# X13_Power_Distribution.net
KiCad netlist of a schematic drawn in EAGLE
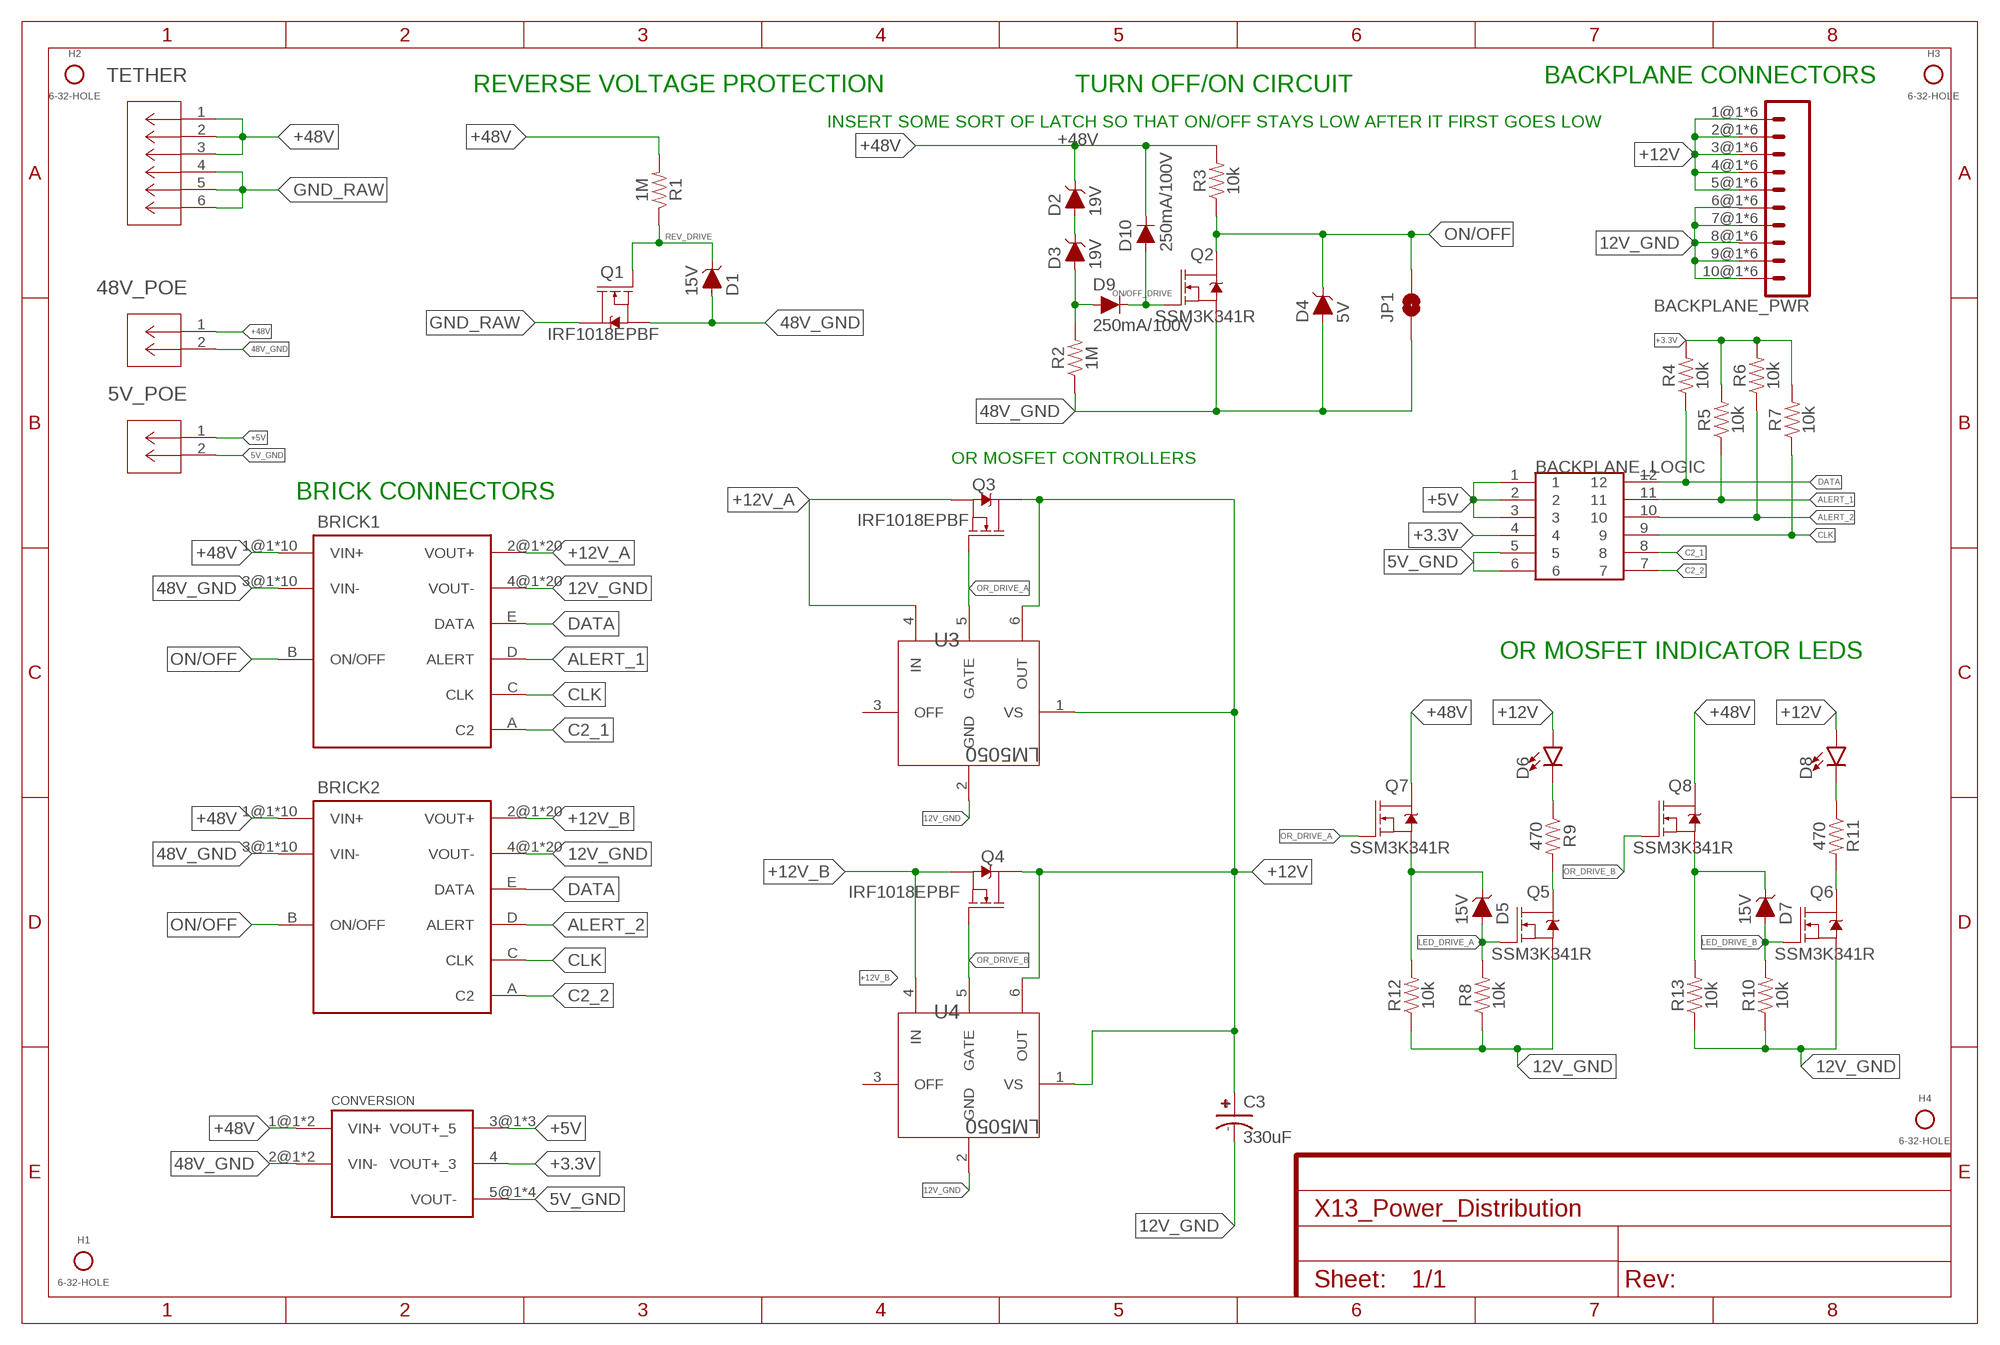
[diagram p0: schematic, sheet 1, part 1 of 2]
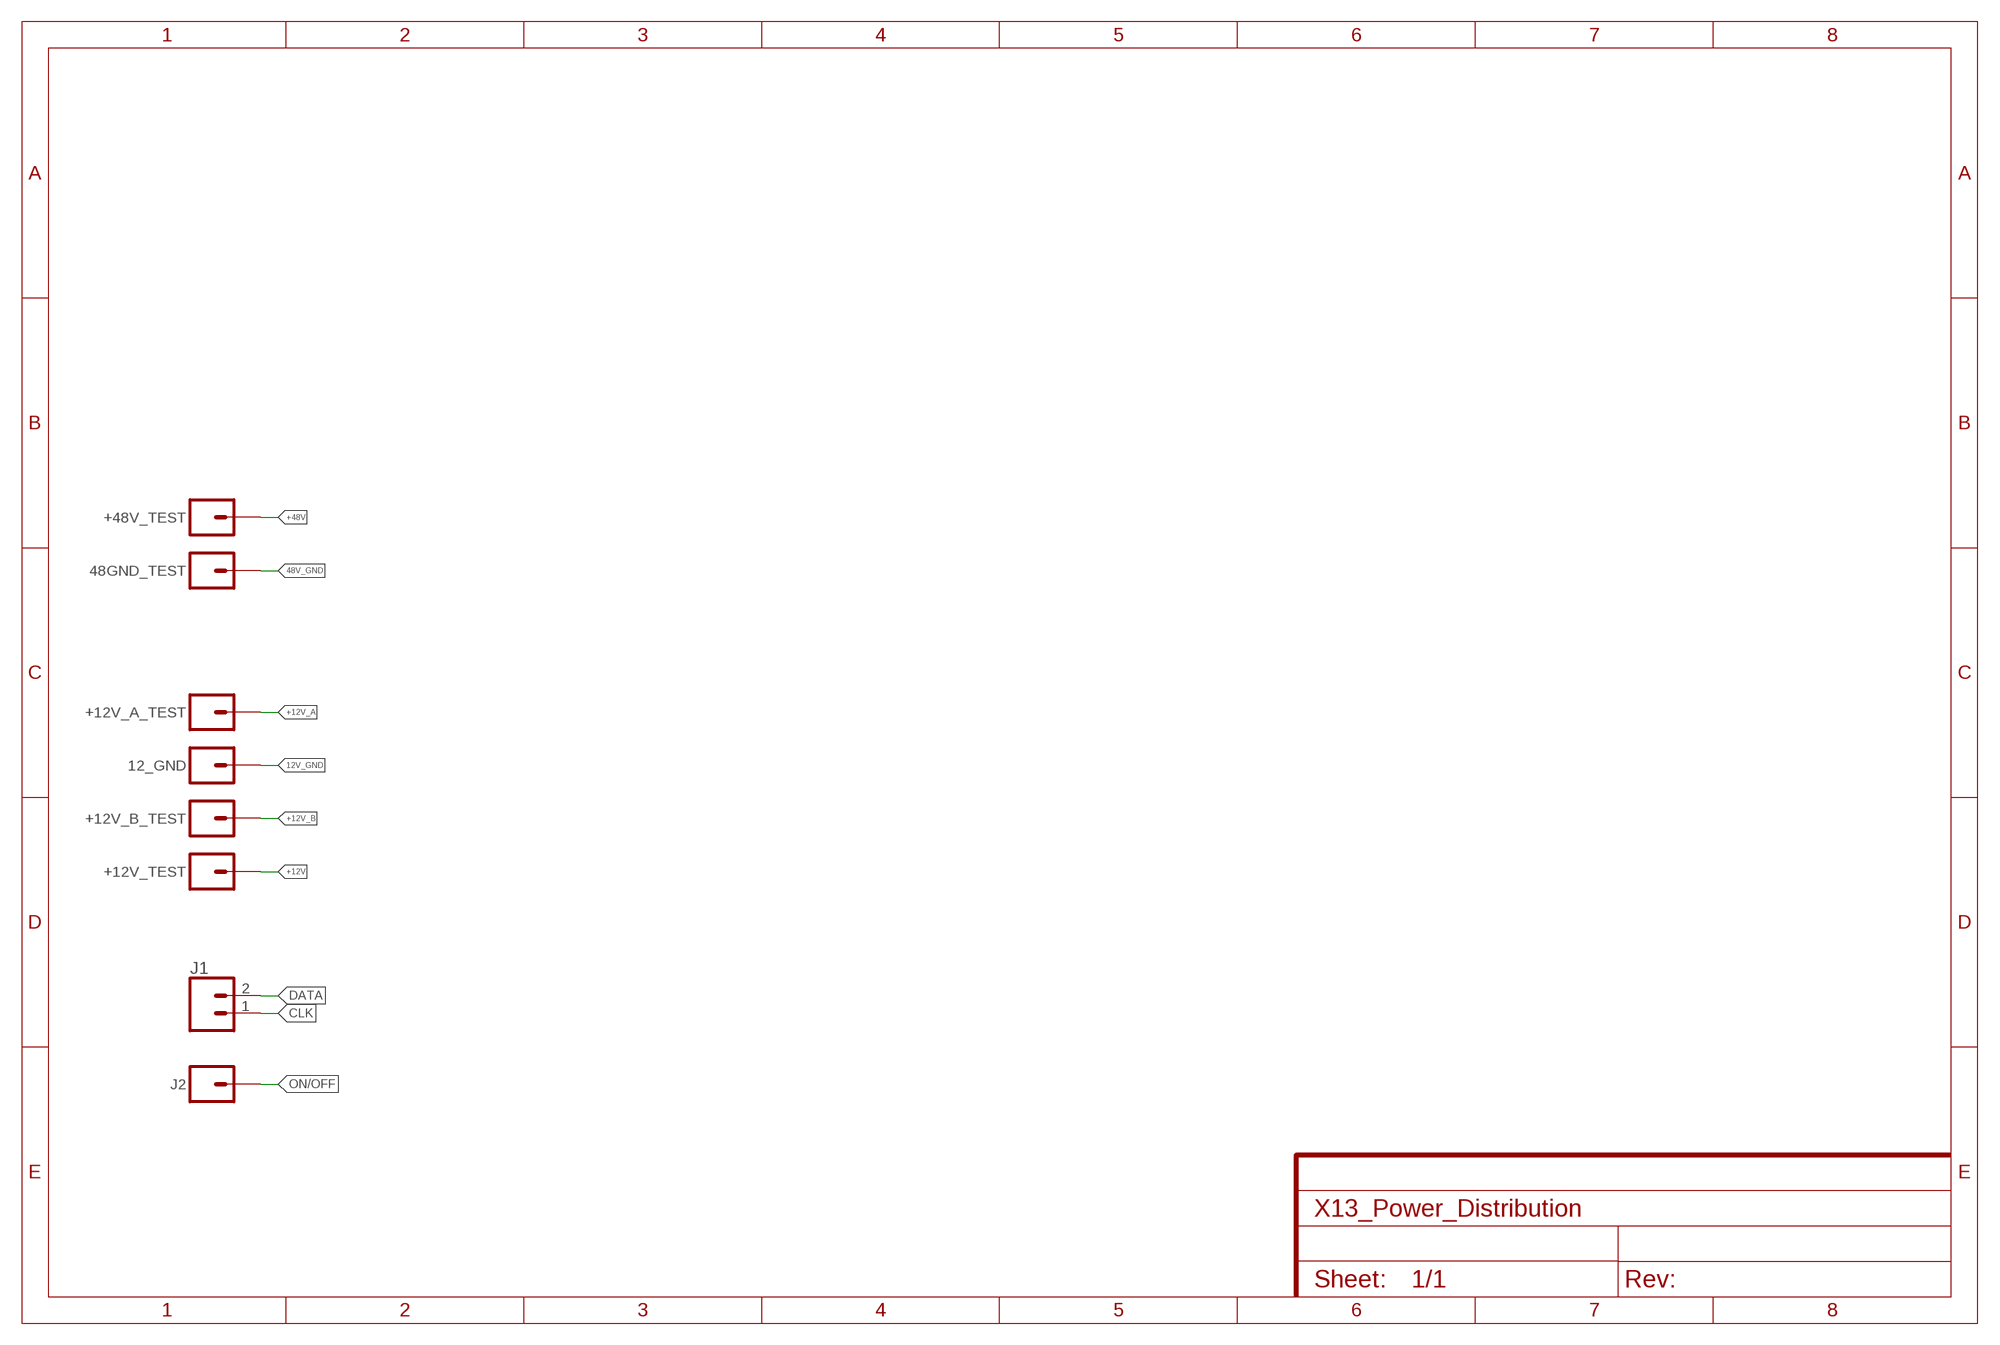
[diagram p1: schematic, sheet 1, part 2 of 2]

(export (version "E")
  (design (tool "Eeschema 10.0.6"))
  (components
    (comp (ref "+12V_A_TEST")
      (value "CONN_01")
      (footprint "eagle-import:1X01")
      (libsource (lib "eagle-import") (part "CONN_01"))
    )
    (comp (ref "+12V_B_TEST")
      (value "CONN_01")
      (footprint "eagle-import:1X01")
      (libsource (lib "eagle-import") (part "CONN_01"))
    )
    (comp (ref "+12V_TEST")
      (value "CONN_01")
      (footprint "eagle-import:1X01")
      (libsource (lib "eagle-import") (part "CONN_01"))
    )
    (comp (ref "+48V_TEST")
      (value "CONN_01")
      (footprint "eagle-import:1X01")
      (libsource (lib "eagle-import") (part "CONN_01"))
    )
    (comp (ref "5V_POE")
      (value "POE_TERMINAL")
      (footprint "eagle-import:CONN2_282834-2_TEC")
      (fields
        (field (name "MANUFACTURER_PART_NUMBER") "282834-2")
        (field (name "COPYRIGHT") "Copyright (C) 2016 Accelerated Designs. All rights reserved")
      )
      (libsource (lib "eagle-import") (part "POE_TERMINAL"))
    )
    (comp (ref "12_GND")
      (value "CONN_01")
      (footprint "eagle-import:1X01")
      (libsource (lib "eagle-import") (part "CONN_01"))
    )
    (comp (ref "48GND_TEST")
      (value "CONN_01")
      (footprint "eagle-import:1X01")
      (libsource (lib "eagle-import") (part "CONN_01"))
    )
    (comp (ref "48V_POE")
      (value "POE_TERMINAL")
      (footprint "eagle-import:CONN2_282834-2_TEC")
      (fields
        (field (name "MANUFACTURER_PART_NUMBER") "282834-2")
        (field (name "COPYRIGHT") "Copyright (C) 2016 Accelerated Designs. All rights reserved")
      )
      (libsource (lib "eagle-import") (part "POE_TERMINAL"))
    )
    (comp (ref "BACKPLANE_LOGIC")
      (value "IPL1-106-01-L-D-K")
      (footprint "eagle-import:IPL1-106-01-L-D-K")
      (libsource (lib "eagle-import") (part "IPL1-106-01-L-D-K"))
    )
    (comp (ref "BACKPLANE_PWR")
      (value "MPPT-10-01-01-L-RA-SD")
      (footprint "eagle-import:MPPT-10-01-01-L-RA-SD")
      (libsource (lib "eagle-import") (part "MPPT-10-01-01-L-RA-SD"))
    )
    (comp (ref "BRICK1")
      (value "DIST2BRICKVER_D2")
      (footprint "eagle-import:DIST2BRICK_D2")
      (libsource (lib "eagle-import") (part "DIST2BRICKVER_D2"))
    )
    (comp (ref "BRICK2")
      (value "DIST2BRICKVER_D2")
      (footprint "eagle-import:DIST2BRICK_D2")
      (libsource (lib "eagle-import") (part "DIST2BRICKVER_D2"))
    )
    (comp (ref "C3")
      (value "330uF")
      (footprint "eagle-import:CAPAE1030X1050N")
      (fields
        (field (name "ARROW_PART_NUMBER") "UCM1H331MNL1GS")
        (field (name "MOUSER_PART_NUMBER") "647-UCM1H331MNL1GS")
      )
      (libsource (lib "eagle-import") (part "UCM1H331MNL1GS"))
    )
    (comp (ref "CONVERSION")
      (value "DIST2CON")
      (footprint "eagle-import:DIST2CON")
      (libsource (lib "eagle-import") (part "DIST2CON"))
    )
    (comp (ref "D1")
      (value "15V")
      (footprint "eagle-import:SOD-323")
      (libsource (lib "eagle-import") (part "DIODE-ZENER-BZT52C3V6S"))
    )
    (comp (ref "D2")
      (value "19V")
      (footprint "eagle-import:SOD-323")
      (libsource (lib "eagle-import") (part "DIODE-ZENER-BZT52C3V6S"))
    )
    (comp (ref "D3")
      (value "19V")
      (footprint "eagle-import:SOD-323")
      (libsource (lib "eagle-import") (part "DIODE-ZENER-BZT52C3V6S"))
    )
    (comp (ref "D4")
      (value "5V")
      (footprint "eagle-import:SOD-323")
      (libsource (lib "eagle-import") (part "DIODE-ZENER-BZT52C3V6S"))
    )
    (comp (ref "D5")
      (value "15V")
      (footprint "eagle-import:SOD-323")
      (libsource (lib "eagle-import") (part "DIODE-ZENER-BZT52C3V6S"))
    )
    (comp (ref "D6")
      (value "LED0603")
      (footprint "eagle-import:LED-0603")
      (libsource (lib "eagle-import") (part "LED0603"))
    )
    (comp (ref "D7")
      (value "15V")
      (footprint "eagle-import:SOD-323")
      (libsource (lib "eagle-import") (part "DIODE-ZENER-BZT52C3V6S"))
    )
    (comp (ref "D8")
      (value "LED0603")
      (footprint "eagle-import:LED-0603")
      (libsource (lib "eagle-import") (part "LED0603"))
    )
    (comp (ref "D9")
      (value "250mA/100V")
      (footprint "eagle-import:SOD-323")
      (libsource (lib "eagle-import") (part "DIODE-BAS16J"))
    )
    (comp (ref "D10")
      (value "250mA/100V")
      (footprint "eagle-import:SOD-323")
      (libsource (lib "eagle-import") (part "DIODE-BAS16J"))
    )
    (comp (ref "H1")
      (value "6-32-HOLE")
      (footprint "eagle-import:6-32-HOLE")
      (libsource (lib "eagle-import") (part "6-32-HOLE"))
    )
    (comp (ref "H2")
      (value "6-32-HOLE")
      (footprint "eagle-import:6-32-HOLE")
      (libsource (lib "eagle-import") (part "6-32-HOLE"))
    )
    (comp (ref "H3")
      (value "6-32-HOLE")
      (footprint "eagle-import:6-32-HOLE")
      (libsource (lib "eagle-import") (part "6-32-HOLE"))
    )
    (comp (ref "H4")
      (value "6-32-HOLE")
      (footprint "eagle-import:6-32-HOLE")
      (libsource (lib "eagle-import") (part "6-32-HOLE"))
    )
    (comp (ref "J1")
      (value "CONN_02")
      (footprint "eagle-import:1X02")
      (libsource (lib "eagle-import") (part "CONN_02"))
    )
    (comp (ref "J2")
      (value "CONN_01")
      (footprint "eagle-import:1X01")
      (libsource (lib "eagle-import") (part "CONN_01"))
    )
    (comp (ref "JP1")
      (value "JUMPER-SMT_2_NO_SILK")
      (footprint "eagle-import:SMT-JUMPER_2_NO_SILK")
      (libsource (lib "eagle-import") (part "JUMPER-SMT_2_NO_SILK"))
    )
    (comp (ref "Q1")
      (value "IRF1018EPBF")
      (footprint "eagle-import:TO263")
      (libsource (lib "eagle-import") (part "IRF1018EPBF"))
    )
    (comp (ref "Q2")
      (value "SSM3K341R")
      (footprint "eagle-import:SOT323")
      (libsource (lib "eagle-import") (part "MOSFET-NCH-2N7002PW"))
    )
    (comp (ref "Q3")
      (value "IRF1018EPBF")
      (footprint "eagle-import:TO263")
      (libsource (lib "eagle-import") (part "IRF1018EPBF"))
    )
    (comp (ref "Q4")
      (value "IRF1018EPBF")
      (footprint "eagle-import:TO263")
      (libsource (lib "eagle-import") (part "IRF1018EPBF"))
    )
    (comp (ref "Q5")
      (value "SSM3K341R")
      (footprint "eagle-import:SOT323")
      (libsource (lib "eagle-import") (part "MOSFET-NCH-2N7002PW"))
    )
    (comp (ref "Q6")
      (value "SSM3K341R")
      (footprint "eagle-import:SOT323")
      (libsource (lib "eagle-import") (part "MOSFET-NCH-2N7002PW"))
    )
    (comp (ref "Q7")
      (value "SSM3K341R")
      (footprint "eagle-import:SOT323")
      (libsource (lib "eagle-import") (part "MOSFET-NCH-2N7002PW"))
    )
    (comp (ref "Q8")
      (value "SSM3K341R")
      (footprint "eagle-import:SOT323")
      (libsource (lib "eagle-import") (part "MOSFET-NCH-2N7002PW"))
    )
    (comp (ref "R1")
      (value "1M")
      (footprint "eagle-import:0603")
      (libsource (lib "eagle-import") (part "RESISTOR0603"))
    )
    (comp (ref "R2")
      (value "1M")
      (footprint "eagle-import:0603")
      (fields (field (name "SPICEPREFIX") "R"))
      (libsource (lib "eagle-import") (part "RESISTOR0603"))
    )
    (comp (ref "R3")
      (value "10k")
      (footprint "eagle-import:0603")
      (fields (field (name "SPICEPREFIX") "R"))
      (libsource (lib "eagle-import") (part "RESISTOR0603"))
    )
    (comp (ref "R4")
      (value "10k")
      (footprint "eagle-import:0603")
      (libsource (lib "eagle-import") (part "RESISTOR0603"))
    )
    (comp (ref "R5")
      (value "10k")
      (footprint "eagle-import:0603")
      (libsource (lib "eagle-import") (part "RESISTOR0603"))
    )
    (comp (ref "R6")
      (value "10k")
      (footprint "eagle-import:0603")
      (libsource (lib "eagle-import") (part "RESISTOR0603"))
    )
    (comp (ref "R7")
      (value "10k")
      (footprint "eagle-import:0603")
      (libsource (lib "eagle-import") (part "RESISTOR0603"))
    )
    (comp (ref "R8")
      (value "10k")
      (footprint "eagle-import:0603")
      (fields (field (name "SPICEPREFIX") "R"))
      (libsource (lib "eagle-import") (part "RESISTOR0603"))
    )
    (comp (ref "R9")
      (value "470")
      (footprint "eagle-import:0603")
      (libsource (lib "eagle-import") (part "RESISTOR0603"))
    )
    (comp (ref "R10")
      (value "10k")
      (footprint "eagle-import:0603")
      (fields (field (name "SPICEPREFIX") "R"))
      (libsource (lib "eagle-import") (part "RESISTOR0603"))
    )
    (comp (ref "R11")
      (value "470")
      (footprint "eagle-import:0603")
      (libsource (lib "eagle-import") (part "RESISTOR0603"))
    )
    (comp (ref "R12")
      (value "10k")
      (footprint "eagle-import:0603")
      (fields (field (name "SPICEPREFIX") "R"))
      (libsource (lib "eagle-import") (part "RESISTOR0603"))
    )
    (comp (ref "R13")
      (value "10k")
      (footprint "eagle-import:0603")
      (fields (field (name "SPICEPREFIX") "R"))
      (libsource (lib "eagle-import") (part "RESISTOR0603"))
    )
    (comp (ref "TETHER")
      (value "48V")
      (footprint "eagle-import:CON6_P5MM_VER_TERM-BLK_TYC")
      (fields (field (name "MANUFACTURER_PART_NUMBER") "796636-6"))
      (libsource (lib "eagle-import") (part "DIST_TO_TETHER"))
    )
    (comp (ref "U3")
      (value "LM5050")
      (footprint "eagle-import:SOT-23-6")
      (fields
        (field (name "MANUFACTURER") "Texas Instruments")
        (field (name "MANUFACTURER_PART_NUMBER") "LM5050MK-1/NOPB")
      )
      (libsource (lib "eagle-import") (part "DIST_OR_CONTROL_ALTMK06A-M"))
    )
    (comp (ref "U4")
      (value "LM5050")
      (footprint "eagle-import:SOT-23-6")
      (fields
        (field (name "MANUFACTURER") "Texas Instruments")
        (field (name "MANUFACTURER_PART_NUMBER") "LM5050MK-1/NOPB")
      )
      (libsource (lib "eagle-import") (part "DIST_OR_CONTROL_ALTMK06A-M"))
    )
  )
  (nets
    (net (code "1") (name "+3.3V") (class "Default")
      (node (ref "BACKPLANE_LOGIC") (pin "4") (pinfunction "4_4") (pintype "bidirectional"))
      (node (ref "CONVERSION") (pin "4") (pinfunction "VOUT+_3_4") (pintype "bidirectional"))
      (node (ref "R4") (pin "2") (pinfunction "2_2") (pintype "passive"))
      (node (ref "R5") (pin "2") (pinfunction "2_2") (pintype "passive"))
      (node (ref "R6") (pin "2") (pinfunction "2_2") (pintype "passive"))
      (node (ref "R7") (pin "2") (pinfunction "2_2") (pintype "passive"))
    )
    (net (code "2") (name "+5V") (class "Default")
      (node (ref "5V_POE") (pin "1") (pinfunction "1_1") (pintype "passive"))
      (node (ref "BACKPLANE_LOGIC") (pin "1") (pinfunction "1_1") (pintype "bidirectional"))
      (node (ref "BACKPLANE_LOGIC") (pin "2") (pinfunction "2_2") (pintype "bidirectional"))
      (node (ref "BACKPLANE_LOGIC") (pin "3") (pinfunction "3_3") (pintype "bidirectional"))
      (node (ref "CONVERSION") (pin "3@1") (pinfunction "VOUT+_5_3@1") (pintype "bidirectional"))
      (node (ref "CONVERSION") (pin "3@2") (pinfunction "VOUT+_5_3@2") (pintype "bidirectional"))
      (node (ref "CONVERSION") (pin "3@3") (pinfunction "VOUT+_5_3@3") (pintype "bidirectional"))
    )
    (net (code "3") (name "+12V") (class "Default")
      (node (ref "+12V_TEST") (pin "1") (pinfunction "1_1") (pintype "passive"))
      (node (ref "BACKPLANE_PWR") (pin "1@1") (pinfunction "1_1@1") (pintype "passive"))
      (node (ref "BACKPLANE_PWR") (pin "1@2") (pinfunction "1_1@2") (pintype "passive"))
      (node (ref "BACKPLANE_PWR") (pin "1@3") (pinfunction "1_1@3") (pintype "passive"))
      (node (ref "BACKPLANE_PWR") (pin "1@4") (pinfunction "1_1@4") (pintype "passive"))
      (node (ref "BACKPLANE_PWR") (pin "1@5") (pinfunction "1_1@5") (pintype "passive"))
      (node (ref "BACKPLANE_PWR") (pin "1@6") (pinfunction "1_1@6") (pintype "passive"))
      (node (ref "BACKPLANE_PWR") (pin "2@1") (pinfunction "2_2@1") (pintype "passive"))
      (node (ref "BACKPLANE_PWR") (pin "2@2") (pinfunction "2_2@2") (pintype "passive"))
      (node (ref "BACKPLANE_PWR") (pin "2@3") (pinfunction "2_2@3") (pintype "passive"))
      (node (ref "BACKPLANE_PWR") (pin "2@4") (pinfunction "2_2@4") (pintype "passive"))
      (node (ref "BACKPLANE_PWR") (pin "2@5") (pinfunction "2_2@5") (pintype "passive"))
      (node (ref "BACKPLANE_PWR") (pin "2@6") (pinfunction "2_2@6") (pintype "passive"))
      (node (ref "BACKPLANE_PWR") (pin "3@1") (pinfunction "3_3@1") (pintype "passive"))
      (node (ref "BACKPLANE_PWR") (pin "3@2") (pinfunction "3_3@2") (pintype "passive"))
      (node (ref "BACKPLANE_PWR") (pin "3@3") (pinfunction "3_3@3") (pintype "passive"))
      (node (ref "BACKPLANE_PWR") (pin "3@4") (pinfunction "3_3@4") (pintype "passive"))
      (node (ref "BACKPLANE_PWR") (pin "3@5") (pinfunction "3_3@5") (pintype "passive"))
      (node (ref "BACKPLANE_PWR") (pin "3@6") (pinfunction "3_3@6") (pintype "passive"))
      (node (ref "BACKPLANE_PWR") (pin "4@1") (pinfunction "4_4@1") (pintype "passive"))
      (node (ref "BACKPLANE_PWR") (pin "4@2") (pinfunction "4_4@2") (pintype "passive"))
      (node (ref "BACKPLANE_PWR") (pin "4@3") (pinfunction "4_4@3") (pintype "passive"))
      (node (ref "BACKPLANE_PWR") (pin "4@4") (pinfunction "4_4@4") (pintype "passive"))
      (node (ref "BACKPLANE_PWR") (pin "4@5") (pinfunction "4_4@5") (pintype "passive"))
      (node (ref "BACKPLANE_PWR") (pin "4@6") (pinfunction "4_4@6") (pintype "passive"))
      (node (ref "BACKPLANE_PWR") (pin "5@1") (pinfunction "5_5@1") (pintype "passive"))
      (node (ref "BACKPLANE_PWR") (pin "5@2") (pinfunction "5_5@2") (pintype "passive"))
      (node (ref "BACKPLANE_PWR") (pin "5@3") (pinfunction "5_5@3") (pintype "passive"))
      (node (ref "BACKPLANE_PWR") (pin "5@4") (pinfunction "5_5@4") (pintype "passive"))
      (node (ref "BACKPLANE_PWR") (pin "5@5") (pinfunction "5_5@5") (pintype "passive"))
      (node (ref "BACKPLANE_PWR") (pin "5@6") (pinfunction "5_5@6") (pintype "passive"))
      (node (ref "C3") (pin "+") (pinfunction "+_+") (pintype "bidirectional"))
      (node (ref "D6") (pin "A") (pinfunction "A_A") (pintype "passive"))
      (node (ref "D8") (pin "A") (pinfunction "A_A") (pintype "passive"))
      (node (ref "Q3") (pin "3") (pinfunction "D_3") (pintype "bidirectional"))
      (node (ref "Q4") (pin "3") (pinfunction "D_3") (pintype "bidirectional"))
      (node (ref "U3") (pin "1") (pinfunction "VS_1") (pintype "passive"))
      (node (ref "U3") (pin "6") (pinfunction "OUT_6") (pintype "output"))
      (node (ref "U4") (pin "1") (pinfunction "VS_1") (pintype "passive"))
      (node (ref "U4") (pin "6") (pinfunction "OUT_6") (pintype "output"))
    )
    (net (code "4") (name "+12V_A") (class "Default")
      (node (ref "+12V_A_TEST") (pin "1") (pinfunction "1_1") (pintype "passive"))
      (node (ref "BRICK1") (pin "2@1") (pinfunction "VOUT+_2@1") (pintype "bidirectional"))
      (node (ref "BRICK1") (pin "2@10") (pinfunction "VOUT+_2@10") (pintype "bidirectional"))
      (node (ref "BRICK1") (pin "2@11") (pinfunction "VOUT+_2@11") (pintype "bidirectional"))
      (node (ref "BRICK1") (pin "2@12") (pinfunction "VOUT+_2@12") (pintype "bidirectional"))
      (node (ref "BRICK1") (pin "2@13") (pinfunction "VOUT+_2@13") (pintype "bidirectional"))
      (node (ref "BRICK1") (pin "2@14") (pinfunction "VOUT+_2@14") (pintype "bidirectional"))
      (node (ref "BRICK1") (pin "2@15") (pinfunction "VOUT+_2@15") (pintype "bidirectional"))
      (node (ref "BRICK1") (pin "2@16") (pinfunction "VOUT+_2@16") (pintype "bidirectional"))
      (node (ref "BRICK1") (pin "2@17") (pinfunction "VOUT+_2@17") (pintype "bidirectional"))
      (node (ref "BRICK1") (pin "2@18") (pinfunction "VOUT+_2@18") (pintype "bidirectional"))
      (node (ref "BRICK1") (pin "2@19") (pinfunction "VOUT+_2@19") (pintype "bidirectional"))
      (node (ref "BRICK1") (pin "2@2") (pinfunction "VOUT+_2@2") (pintype "bidirectional"))
      (node (ref "BRICK1") (pin "2@20") (pinfunction "VOUT+_2@20") (pintype "bidirectional"))
      (node (ref "BRICK1") (pin "2@3") (pinfunction "VOUT+_2@3") (pintype "bidirectional"))
      (node (ref "BRICK1") (pin "2@4") (pinfunction "VOUT+_2@4") (pintype "bidirectional"))
      (node (ref "BRICK1") (pin "2@5") (pinfunction "VOUT+_2@5") (pintype "bidirectional"))
      (node (ref "BRICK1") (pin "2@6") (pinfunction "VOUT+_2@6") (pintype "bidirectional"))
      (node (ref "BRICK1") (pin "2@7") (pinfunction "VOUT+_2@7") (pintype "bidirectional"))
      (node (ref "BRICK1") (pin "2@8") (pinfunction "VOUT+_2@8") (pintype "bidirectional"))
      (node (ref "BRICK1") (pin "2@9") (pinfunction "VOUT+_2@9") (pintype "bidirectional"))
      (node (ref "Q3") (pin "2") (pinfunction "S_2") (pintype "bidirectional"))
      (node (ref "U3") (pin "4") (pinfunction "IN_4") (pintype "input"))
    )
    (net (code "5") (name "+12V_B") (class "Default")
      (node (ref "+12V_B_TEST") (pin "1") (pinfunction "1_1") (pintype "passive"))
      (node (ref "BRICK2") (pin "2@1") (pinfunction "VOUT+_2@1") (pintype "bidirectional"))
      (node (ref "BRICK2") (pin "2@10") (pinfunction "VOUT+_2@10") (pintype "bidirectional"))
      (node (ref "BRICK2") (pin "2@11") (pinfunction "VOUT+_2@11") (pintype "bidirectional"))
      (node (ref "BRICK2") (pin "2@12") (pinfunction "VOUT+_2@12") (pintype "bidirectional"))
      (node (ref "BRICK2") (pin "2@13") (pinfunction "VOUT+_2@13") (pintype "bidirectional"))
      (node (ref "BRICK2") (pin "2@14") (pinfunction "VOUT+_2@14") (pintype "bidirectional"))
      (node (ref "BRICK2") (pin "2@15") (pinfunction "VOUT+_2@15") (pintype "bidirectional"))
      (node (ref "BRICK2") (pin "2@16") (pinfunction "VOUT+_2@16") (pintype "bidirectional"))
      (node (ref "BRICK2") (pin "2@17") (pinfunction "VOUT+_2@17") (pintype "bidirectional"))
      (node (ref "BRICK2") (pin "2@18") (pinfunction "VOUT+_2@18") (pintype "bidirectional"))
      (node (ref "BRICK2") (pin "2@19") (pinfunction "VOUT+_2@19") (pintype "bidirectional"))
      (node (ref "BRICK2") (pin "2@2") (pinfunction "VOUT+_2@2") (pintype "bidirectional"))
      (node (ref "BRICK2") (pin "2@20") (pinfunction "VOUT+_2@20") (pintype "bidirectional"))
      (node (ref "BRICK2") (pin "2@3") (pinfunction "VOUT+_2@3") (pintype "bidirectional"))
      (node (ref "BRICK2") (pin "2@4") (pinfunction "VOUT+_2@4") (pintype "bidirectional"))
      (node (ref "BRICK2") (pin "2@5") (pinfunction "VOUT+_2@5") (pintype "bidirectional"))
      (node (ref "BRICK2") (pin "2@6") (pinfunction "VOUT+_2@6") (pintype "bidirectional"))
      (node (ref "BRICK2") (pin "2@7") (pinfunction "VOUT+_2@7") (pintype "bidirectional"))
      (node (ref "BRICK2") (pin "2@8") (pinfunction "VOUT+_2@8") (pintype "bidirectional"))
      (node (ref "BRICK2") (pin "2@9") (pinfunction "VOUT+_2@9") (pintype "bidirectional"))
      (node (ref "Q4") (pin "2") (pinfunction "S_2") (pintype "bidirectional"))
      (node (ref "U4") (pin "4") (pinfunction "IN_4") (pintype "input"))
    )
    (net (code "6") (name "+48V") (class "Default")
      (node (ref "+48V_TEST") (pin "1") (pinfunction "1_1") (pintype "passive"))
      (node (ref "48V_POE") (pin "1") (pinfunction "1_1") (pintype "passive"))
      (node (ref "BRICK1") (pin "1@1") (pinfunction "VIN+_1@1") (pintype "bidirectional"))
      (node (ref "BRICK1") (pin "1@10") (pinfunction "VIN+_1@10") (pintype "bidirectional"))
      (node (ref "BRICK1") (pin "1@2") (pinfunction "VIN+_1@2") (pintype "bidirectional"))
      (node (ref "BRICK1") (pin "1@3") (pinfunction "VIN+_1@3") (pintype "bidirectional"))
      (node (ref "BRICK1") (pin "1@4") (pinfunction "VIN+_1@4") (pintype "bidirectional"))
      (node (ref "BRICK1") (pin "1@5") (pinfunction "VIN+_1@5") (pintype "bidirectional"))
      (node (ref "BRICK1") (pin "1@6") (pinfunction "VIN+_1@6") (pintype "bidirectional"))
      (node (ref "BRICK1") (pin "1@7") (pinfunction "VIN+_1@7") (pintype "bidirectional"))
      (node (ref "BRICK1") (pin "1@8") (pinfunction "VIN+_1@8") (pintype "bidirectional"))
      (node (ref "BRICK1") (pin "1@9") (pinfunction "VIN+_1@9") (pintype "bidirectional"))
      (node (ref "BRICK2") (pin "1@1") (pinfunction "VIN+_1@1") (pintype "bidirectional"))
      (node (ref "BRICK2") (pin "1@10") (pinfunction "VIN+_1@10") (pintype "bidirectional"))
      (node (ref "BRICK2") (pin "1@2") (pinfunction "VIN+_1@2") (pintype "bidirectional"))
      (node (ref "BRICK2") (pin "1@3") (pinfunction "VIN+_1@3") (pintype "bidirectional"))
      (node (ref "BRICK2") (pin "1@4") (pinfunction "VIN+_1@4") (pintype "bidirectional"))
      (node (ref "BRICK2") (pin "1@5") (pinfunction "VIN+_1@5") (pintype "bidirectional"))
      (node (ref "BRICK2") (pin "1@6") (pinfunction "VIN+_1@6") (pintype "bidirectional"))
      (node (ref "BRICK2") (pin "1@7") (pinfunction "VIN+_1@7") (pintype "bidirectional"))
      (node (ref "BRICK2") (pin "1@8") (pinfunction "VIN+_1@8") (pintype "bidirectional"))
      (node (ref "BRICK2") (pin "1@9") (pinfunction "VIN+_1@9") (pintype "bidirectional"))
      (node (ref "CONVERSION") (pin "1@1") (pinfunction "VIN+_1@1") (pintype "bidirectional"))
      (node (ref "CONVERSION") (pin "1@2") (pinfunction "VIN+_1@2") (pintype "bidirectional"))
      (node (ref "D10") (pin "C") (pinfunction "C_C") (pintype "passive"))
      (node (ref "D2") (pin "C") (pinfunction "C_C") (pintype "passive"))
      (node (ref "Q7") (pin "3") (pinfunction "D_3") (pintype "bidirectional"))
      (node (ref "Q8") (pin "3") (pinfunction "D_3") (pintype "bidirectional"))
      (node (ref "R1") (pin "2") (pinfunction "2_2") (pintype "passive"))
      (node (ref "R3") (pin "2") (pinfunction "2_2") (pintype "passive"))
      (node (ref "TETHER") (pin "1") (pinfunction "1_1") (pintype "passive"))
      (node (ref "TETHER") (pin "2") (pinfunction "2_2") (pintype "passive"))
      (node (ref "TETHER") (pin "3") (pinfunction "3_3") (pintype "passive"))
    )
    (net (code "7") (name "/ON{slash}OFF_DRIVE") (class "Default")
      (node (ref "D10") (pin "A") (pinfunction "A_A") (pintype "passive"))
      (node (ref "D9") (pin "C") (pinfunction "C_C") (pintype "passive"))
      (node (ref "Q2") (pin "1") (pinfunction "G_1") (pintype "bidirectional"))
    )
    (net (code "8") (name "/REV_DRIVE") (class "Default")
      (node (ref "D1") (pin "C") (pinfunction "C_C") (pintype "passive"))
      (node (ref "Q1") (pin "1") (pinfunction "G_1") (pintype "bidirectional"))
      (node (ref "R1") (pin "1") (pinfunction "1_1") (pintype "passive"))
    )
    (net (code "9") (name "5V_GND") (class "Default")
      (node (ref "5V_POE") (pin "2") (pinfunction "2_2") (pintype "passive"))
      (node (ref "BACKPLANE_LOGIC") (pin "5") (pinfunction "5_5") (pintype "bidirectional"))
      (node (ref "BACKPLANE_LOGIC") (pin "6") (pinfunction "6_6") (pintype "bidirectional"))
      (node (ref "CONVERSION") (pin "5@1") (pinfunction "VOUT-_5@1") (pintype "bidirectional"))
      (node (ref "CONVERSION") (pin "5@2") (pinfunction "VOUT-_5@2") (pintype "bidirectional"))
      (node (ref "CONVERSION") (pin "5@3") (pinfunction "VOUT-_5@3") (pintype "bidirectional"))
      (node (ref "CONVERSION") (pin "5@4") (pinfunction "VOUT-_5@4") (pintype "bidirectional"))
    )
    (net (code "10") (name "12V_GND") (class "Default")
      (node (ref "12_GND") (pin "1") (pinfunction "1_1") (pintype "passive"))
      (node (ref "BACKPLANE_PWR") (pin "10@1") (pinfunction "10_10@1") (pintype "passive"))
      (node (ref "BACKPLANE_PWR") (pin "10@2") (pinfunction "10_10@2") (pintype "passive"))
      (node (ref "BACKPLANE_PWR") (pin "10@3") (pinfunction "10_10@3") (pintype "passive"))
      (node (ref "BACKPLANE_PWR") (pin "10@4") (pinfunction "10_10@4") (pintype "passive"))
      (node (ref "BACKPLANE_PWR") (pin "10@5") (pinfunction "10_10@5") (pintype "passive"))
      (node (ref "BACKPLANE_PWR") (pin "10@6") (pinfunction "10_10@6") (pintype "passive"))
      (node (ref "BACKPLANE_PWR") (pin "6@1") (pinfunction "6_6@1") (pintype "passive"))
      (node (ref "BACKPLANE_PWR") (pin "6@2") (pinfunction "6_6@2") (pintype "passive"))
      (node (ref "BACKPLANE_PWR") (pin "6@3") (pinfunction "6_6@3") (pintype "passive"))
      (node (ref "BACKPLANE_PWR") (pin "6@4") (pinfunction "6_6@4") (pintype "passive"))
      (node (ref "BACKPLANE_PWR") (pin "6@5") (pinfunction "6_6@5") (pintype "passive"))
      (node (ref "BACKPLANE_PWR") (pin "6@6") (pinfunction "6_6@6") (pintype "passive"))
      (node (ref "BACKPLANE_PWR") (pin "7@1") (pinfunction "7_7@1") (pintype "passive"))
      (node (ref "BACKPLANE_PWR") (pin "7@2") (pinfunction "7_7@2") (pintype "passive"))
      (node (ref "BACKPLANE_PWR") (pin "7@3") (pinfunction "7_7@3") (pintype "passive"))
      (node (ref "BACKPLANE_PWR") (pin "7@4") (pinfunction "7_7@4") (pintype "passive"))
      (node (ref "BACKPLANE_PWR") (pin "7@5") (pinfunction "7_7@5") (pintype "passive"))
      (node (ref "BACKPLANE_PWR") (pin "7@6") (pinfunction "7_7@6") (pintype "passive"))
      (node (ref "BACKPLANE_PWR") (pin "8@1") (pinfunction "8_8@1") (pintype "passive"))
      (node (ref "BACKPLANE_PWR") (pin "8@2") (pinfunction "8_8@2") (pintype "passive"))
      (node (ref "BACKPLANE_PWR") (pin "8@3") (pinfunction "8_8@3") (pintype "passive"))
      (node (ref "BACKPLANE_PWR") (pin "8@4") (pinfunction "8_8@4") (pintype "passive"))
      (node (ref "BACKPLANE_PWR") (pin "8@5") (pinfunction "8_8@5") (pintype "passive"))
      (node (ref "BACKPLANE_PWR") (pin "8@6") (pinfunction "8_8@6") (pintype "passive"))
      (node (ref "BACKPLANE_PWR") (pin "9@1") (pinfunction "9_9@1") (pintype "passive"))
      (node (ref "BACKPLANE_PWR") (pin "9@2") (pinfunction "9_9@2") (pintype "passive"))
      (node (ref "BACKPLANE_PWR") (pin "9@3") (pinfunction "9_9@3") (pintype "passive"))
      (node (ref "BACKPLANE_PWR") (pin "9@4") (pinfunction "9_9@4") (pintype "passive"))
      (node (ref "BACKPLANE_PWR") (pin "9@5") (pinfunction "9_9@5") (pintype "passive"))
      (node (ref "BACKPLANE_PWR") (pin "9@6") (pinfunction "9_9@6") (pintype "passive"))
      (node (ref "BRICK1") (pin "4@1") (pinfunction "VOUT-_4@1") (pintype "bidirectional"))
      (node (ref "BRICK1") (pin "4@10") (pinfunction "VOUT-_4@10") (pintype "bidirectional"))
      (node (ref "BRICK1") (pin "4@11") (pinfunction "VOUT-_4@11") (pintype "bidirectional"))
      (node (ref "BRICK1") (pin "4@12") (pinfunction "VOUT-_4@12") (pintype "bidirectional"))
      (node (ref "BRICK1") (pin "4@13") (pinfunction "VOUT-_4@13") (pintype "bidirectional"))
      (node (ref "BRICK1") (pin "4@14") (pinfunction "VOUT-_4@14") (pintype "bidirectional"))
      (node (ref "BRICK1") (pin "4@15") (pinfunction "VOUT-_4@15") (pintype "bidirectional"))
      (node (ref "BRICK1") (pin "4@16") (pinfunction "VOUT-_4@16") (pintype "bidirectional"))
      (node (ref "BRICK1") (pin "4@17") (pinfunction "VOUT-_4@17") (pintype "bidirectional"))
      (node (ref "BRICK1") (pin "4@18") (pinfunction "VOUT-_4@18") (pintype "bidirectional"))
      (node (ref "BRICK1") (pin "4@19") (pinfunction "VOUT-_4@19") (pintype "bidirectional"))
      (node (ref "BRICK1") (pin "4@2") (pinfunction "VOUT-_4@2") (pintype "bidirectional"))
      (node (ref "BRICK1") (pin "4@20") (pinfunction "VOUT-_4@20") (pintype "bidirectional"))
      (node (ref "BRICK1") (pin "4@3") (pinfunction "VOUT-_4@3") (pintype "bidirectional"))
      (node (ref "BRICK1") (pin "4@4") (pinfunction "VOUT-_4@4") (pintype "bidirectional"))
      (node (ref "BRICK1") (pin "4@5") (pinfunction "VOUT-_4@5") (pintype "bidirectional"))
      (node (ref "BRICK1") (pin "4@6") (pinfunction "VOUT-_4@6") (pintype "bidirectional"))
      (node (ref "BRICK1") (pin "4@7") (pinfunction "VOUT-_4@7") (pintype "bidirectional"))
      (node (ref "BRICK1") (pin "4@8") (pinfunction "VOUT-_4@8") (pintype "bidirectional"))
      (node (ref "BRICK1") (pin "4@9") (pinfunction "VOUT-_4@9") (pintype "bidirectional"))
      (node (ref "BRICK2") (pin "4@1") (pinfunction "VOUT-_4@1") (pintype "bidirectional"))
      (node (ref "BRICK2") (pin "4@10") (pinfunction "VOUT-_4@10") (pintype "bidirectional"))
      (node (ref "BRICK2") (pin "4@11") (pinfunction "VOUT-_4@11") (pintype "bidirectional"))
      (node (ref "BRICK2") (pin "4@12") (pinfunction "VOUT-_4@12") (pintype "bidirectional"))
      (node (ref "BRICK2") (pin "4@13") (pinfunction "VOUT-_4@13") (pintype "bidirectional"))
      (node (ref "BRICK2") (pin "4@14") (pinfunction "VOUT-_4@14") (pintype "bidirectional"))
      (node (ref "BRICK2") (pin "4@15") (pinfunction "VOUT-_4@15") (pintype "bidirectional"))
      (node (ref "BRICK2") (pin "4@16") (pinfunction "VOUT-_4@16") (pintype "bidirectional"))
      (node (ref "BRICK2") (pin "4@17") (pinfunction "VOUT-_4@17") (pintype "bidirectional"))
      (node (ref "BRICK2") (pin "4@18") (pinfunction "VOUT-_4@18") (pintype "bidirectional"))
      (node (ref "BRICK2") (pin "4@19") (pinfunction "VOUT-_4@19") (pintype "bidirectional"))
      (node (ref "BRICK2") (pin "4@2") (pinfunction "VOUT-_4@2") (pintype "bidirectional"))
      (node (ref "BRICK2") (pin "4@20") (pinfunction "VOUT-_4@20") (pintype "bidirectional"))
      (node (ref "BRICK2") (pin "4@3") (pinfunction "VOUT-_4@3") (pintype "bidirectional"))
      (node (ref "BRICK2") (pin "4@4") (pinfunction "VOUT-_4@4") (pintype "bidirectional"))
      (node (ref "BRICK2") (pin "4@5") (pinfunction "VOUT-_4@5") (pintype "bidirectional"))
      (node (ref "BRICK2") (pin "4@6") (pinfunction "VOUT-_4@6") (pintype "bidirectional"))
      (node (ref "BRICK2") (pin "4@7") (pinfunction "VOUT-_4@7") (pintype "bidirectional"))
      (node (ref "BRICK2") (pin "4@8") (pinfunction "VOUT-_4@8") (pintype "bidirectional"))
      (node (ref "BRICK2") (pin "4@9") (pinfunction "VOUT-_4@9") (pintype "bidirectional"))
      (node (ref "C3") (pin "-") (pinfunction "-_-") (pintype "bidirectional"))
      (node (ref "Q5") (pin "2") (pinfunction "S_2") (pintype "bidirectional"))
      (node (ref "Q6") (pin "2") (pinfunction "S_2") (pintype "bidirectional"))
      (node (ref "R10") (pin "1") (pinfunction "1_1") (pintype "passive"))
      (node (ref "R12") (pin "1") (pinfunction "1_1") (pintype "passive"))
      (node (ref "R13") (pin "1") (pinfunction "1_1") (pintype "passive"))
      (node (ref "R8") (pin "1") (pinfunction "1_1") (pintype "passive"))
      (node (ref "U3") (pin "2") (pinfunction "GND_2") (pintype "power_in"))
      (node (ref "U4") (pin "2") (pinfunction "GND_2") (pintype "power_in"))
    )
    (net (code "11") (name "48V_GND") (class "Default")
      (node (ref "48GND_TEST") (pin "1") (pinfunction "1_1") (pintype "passive"))
      (node (ref "48V_POE") (pin "2") (pinfunction "2_2") (pintype "passive"))
      (node (ref "BRICK1") (pin "3@1") (pinfunction "VIN-_3@1") (pintype "bidirectional"))
      (node (ref "BRICK1") (pin "3@10") (pinfunction "VIN-_3@10") (pintype "bidirectional"))
      (node (ref "BRICK1") (pin "3@2") (pinfunction "VIN-_3@2") (pintype "bidirectional"))
      (node (ref "BRICK1") (pin "3@3") (pinfunction "VIN-_3@3") (pintype "bidirectional"))
      (node (ref "BRICK1") (pin "3@4") (pinfunction "VIN-_3@4") (pintype "bidirectional"))
      (node (ref "BRICK1") (pin "3@5") (pinfunction "VIN-_3@5") (pintype "bidirectional"))
      (node (ref "BRICK1") (pin "3@6") (pinfunction "VIN-_3@6") (pintype "bidirectional"))
      (node (ref "BRICK1") (pin "3@7") (pinfunction "VIN-_3@7") (pintype "bidirectional"))
      (node (ref "BRICK1") (pin "3@8") (pinfunction "VIN-_3@8") (pintype "bidirectional"))
      (node (ref "BRICK1") (pin "3@9") (pinfunction "VIN-_3@9") (pintype "bidirectional"))
      (node (ref "BRICK2") (pin "3@1") (pinfunction "VIN-_3@1") (pintype "bidirectional"))
      (node (ref "BRICK2") (pin "3@10") (pinfunction "VIN-_3@10") (pintype "bidirectional"))
      (node (ref "BRICK2") (pin "3@2") (pinfunction "VIN-_3@2") (pintype "bidirectional"))
      (node (ref "BRICK2") (pin "3@3") (pinfunction "VIN-_3@3") (pintype "bidirectional"))
      (node (ref "BRICK2") (pin "3@4") (pinfunction "VIN-_3@4") (pintype "bidirectional"))
      (node (ref "BRICK2") (pin "3@5") (pinfunction "VIN-_3@5") (pintype "bidirectional"))
      (node (ref "BRICK2") (pin "3@6") (pinfunction "VIN-_3@6") (pintype "bidirectional"))
      (node (ref "BRICK2") (pin "3@7") (pinfunction "VIN-_3@7") (pintype "bidirectional"))
      (node (ref "BRICK2") (pin "3@8") (pinfunction "VIN-_3@8") (pintype "bidirectional"))
      (node (ref "BRICK2") (pin "3@9") (pinfunction "VIN-_3@9") (pintype "bidirectional"))
      (node (ref "CONVERSION") (pin "2@1") (pinfunction "VIN-_2@1") (pintype "bidirectional"))
      (node (ref "CONVERSION") (pin "2@2") (pinfunction "VIN-_2@2") (pintype "bidirectional"))
      (node (ref "D1") (pin "A") (pinfunction "A_A") (pintype "passive"))
      (node (ref "D4") (pin "A") (pinfunction "A_A") (pintype "passive"))
      (node (ref "JP1") (pin "1") (pinfunction "1_1") (pintype "passive"))
      (node (ref "Q1") (pin "2") (pinfunction "S_2") (pintype "bidirectional"))
      (node (ref "Q2") (pin "2") (pinfunction "S_2") (pintype "bidirectional"))
      (node (ref "R2") (pin "1") (pinfunction "1_1") (pintype "passive"))
    )
    (net (code "12") (name "ALERT_1") (class "Default")
      (node (ref "BACKPLANE_LOGIC") (pin "11") (pinfunction "11_11") (pintype "bidirectional"))
      (node (ref "BRICK1") (pin "D") (pinfunction "ALERT_D") (pintype "bidirectional"))
      (node (ref "R5") (pin "1") (pinfunction "1_1") (pintype "passive"))
    )
    (net (code "13") (name "ALERT_2") (class "Default")
      (node (ref "BACKPLANE_LOGIC") (pin "10") (pinfunction "10_10") (pintype "bidirectional"))
      (node (ref "BRICK2") (pin "D") (pinfunction "ALERT_D") (pintype "bidirectional"))
      (node (ref "R6") (pin "1") (pinfunction "1_1") (pintype "passive"))
    )
    (net (code "14") (name "C2_1") (class "Default")
      (node (ref "BACKPLANE_LOGIC") (pin "8") (pinfunction "8_8") (pintype "bidirectional"))
      (node (ref "BRICK1") (pin "A") (pinfunction "C2_A") (pintype "bidirectional"))
    )
    (net (code "15") (name "C2_2") (class "Default")
      (node (ref "BACKPLANE_LOGIC") (pin "7") (pinfunction "7_7") (pintype "bidirectional"))
      (node (ref "BRICK2") (pin "A") (pinfunction "C2_A") (pintype "bidirectional"))
    )
    (net (code "16") (name "CLK") (class "Default")
      (node (ref "BACKPLANE_LOGIC") (pin "9") (pinfunction "9_9") (pintype "bidirectional"))
      (node (ref "BRICK1") (pin "C") (pinfunction "CLK_C") (pintype "bidirectional"))
      (node (ref "BRICK2") (pin "C") (pinfunction "CLK_C") (pintype "bidirectional"))
      (node (ref "J1") (pin "1") (pinfunction "1_1") (pintype "passive"))
      (node (ref "R7") (pin "1") (pinfunction "1_1") (pintype "passive"))
    )
    (net (code "17") (name "DATA") (class "Default")
      (node (ref "BACKPLANE_LOGIC") (pin "12") (pinfunction "12_12") (pintype "bidirectional"))
      (node (ref "BRICK1") (pin "E") (pinfunction "DATA_E") (pintype "bidirectional"))
      (node (ref "BRICK2") (pin "E") (pinfunction "DATA_E") (pintype "bidirectional"))
      (node (ref "J1") (pin "2") (pinfunction "2_2") (pintype "passive"))
      (node (ref "R4") (pin "1") (pinfunction "1_1") (pintype "passive"))
    )
    (net (code "18") (name "GND_RAW") (class "Default")
      (node (ref "Q1") (pin "3") (pinfunction "D_3") (pintype "bidirectional"))
      (node (ref "TETHER") (pin "4") (pinfunction "4_4") (pintype "passive"))
      (node (ref "TETHER") (pin "5") (pinfunction "5_5") (pintype "passive"))
      (node (ref "TETHER") (pin "6") (pinfunction "6_6") (pintype "passive"))
    )
    (net (code "19") (name "LED_DRIVE_A") (class "Default")
      (node (ref "D5") (pin "A") (pinfunction "A_A") (pintype "passive"))
      (node (ref "Q5") (pin "1") (pinfunction "G_1") (pintype "bidirectional"))
      (node (ref "R8") (pin "2") (pinfunction "2_2") (pintype "passive"))
    )
    (net (code "20") (name "LED_DRIVE_B") (class "Default")
      (node (ref "D7") (pin "A") (pinfunction "A_A") (pintype "passive"))
      (node (ref "Q6") (pin "1") (pinfunction "G_1") (pintype "bidirectional"))
      (node (ref "R10") (pin "2") (pinfunction "2_2") (pintype "passive"))
    )
    (net (code "21") (name "Net-(D2-PadA)") (class "Default")
      (node (ref "D2") (pin "A") (pinfunction "A_A") (pintype "passive"))
      (node (ref "D3") (pin "C") (pinfunction "C_C") (pintype "passive"))
    )
    (net (code "22") (name "Net-(D3-PadA)") (class "Default")
      (node (ref "D3") (pin "A") (pinfunction "A_A") (pintype "passive"))
      (node (ref "D9") (pin "A") (pinfunction "A_A") (pintype "passive"))
      (node (ref "R2") (pin "2") (pinfunction "2_2") (pintype "passive"))
    )
    (net (code "23") (name "Net-(D6-PadC)") (class "Default")
      (node (ref "D6") (pin "C") (pinfunction "C_C") (pintype "passive"))
      (node (ref "R9") (pin "1") (pinfunction "1_1") (pintype "passive"))
    )
    (net (code "24") (name "Net-(D8-PadC)") (class "Default")
      (node (ref "D8") (pin "C") (pinfunction "C_C") (pintype "passive"))
      (node (ref "R11") (pin "1") (pinfunction "1_1") (pintype "passive"))
    )
    (net (code "25") (name "Net-(Q5-D)") (class "Default")
      (node (ref "Q5") (pin "3") (pinfunction "D_3") (pintype "bidirectional"))
      (node (ref "R9") (pin "2") (pinfunction "2_2") (pintype "passive"))
    )
    (net (code "26") (name "Net-(Q6-D)") (class "Default")
      (node (ref "Q6") (pin "3") (pinfunction "D_3") (pintype "bidirectional"))
      (node (ref "R11") (pin "2") (pinfunction "2_2") (pintype "passive"))
    )
    (net (code "27") (name "Net-(Q7-S)") (class "Default")
      (node (ref "D5") (pin "C") (pinfunction "C_C") (pintype "passive"))
      (node (ref "Q7") (pin "2") (pinfunction "S_2") (pintype "bidirectional"))
      (node (ref "R12") (pin "2") (pinfunction "2_2") (pintype "passive"))
    )
    (net (code "28") (name "Net-(Q8-S)") (class "Default")
      (node (ref "D7") (pin "C") (pinfunction "C_C") (pintype "passive"))
      (node (ref "Q8") (pin "2") (pinfunction "S_2") (pintype "bidirectional"))
      (node (ref "R13") (pin "2") (pinfunction "2_2") (pintype "passive"))
    )
    (net (code "29") (name "ON{slash}OFF") (class "Default")
      (node (ref "BRICK1") (pin "B") (pinfunction "ON/OFF_B") (pintype "bidirectional"))
      (node (ref "BRICK2") (pin "B") (pinfunction "ON/OFF_B") (pintype "bidirectional"))
      (node (ref "D4") (pin "C") (pinfunction "C_C") (pintype "passive"))
      (node (ref "J2") (pin "1") (pinfunction "1_1") (pintype "passive"))
      (node (ref "JP1") (pin "2") (pinfunction "2_2") (pintype "passive"))
      (node (ref "Q2") (pin "3") (pinfunction "D_3") (pintype "bidirectional"))
      (node (ref "R3") (pin "1") (pinfunction "1_1") (pintype "passive"))
    )
    (net (code "30") (name "OR_DRIVE_A") (class "Default")
      (node (ref "Q3") (pin "1") (pinfunction "G_1") (pintype "bidirectional"))
      (node (ref "Q7") (pin "1") (pinfunction "G_1") (pintype "bidirectional"))
      (node (ref "U3") (pin "5") (pinfunction "GATE_5") (pintype "passive"))
    )
    (net (code "31") (name "OR_DRIVE_B") (class "Default")
      (node (ref "Q4") (pin "1") (pinfunction "G_1") (pintype "bidirectional"))
      (node (ref "Q8") (pin "1") (pinfunction "G_1") (pintype "bidirectional"))
      (node (ref "U4") (pin "5") (pinfunction "GATE_5") (pintype "passive"))
    )
    (net (code "32") (name "unconnected-(U3-OFF-Pad3)") (class "Default")
      (node (ref "U3") (pin "3") (pinfunction "OFF_3") (pintype "passive"))
    )
    (net (code "33") (name "unconnected-(U4-OFF-Pad3)") (class "Default")
      (node (ref "U4") (pin "3") (pinfunction "OFF_3") (pintype "passive"))
    )
  )
)
